# TIMB-E010-2.net
KiCad netlist of a schematic drawn in EAGLE
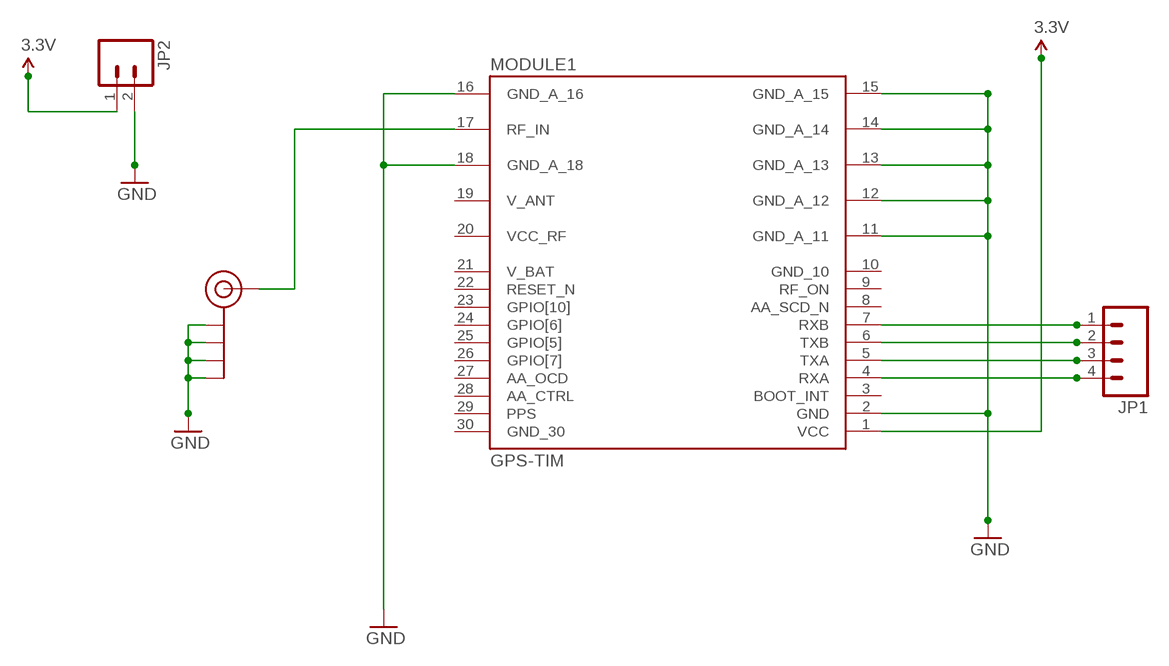
[diagram p0: schematic, sheet 1]

(export (version "E")
  (design (tool "Eeschema 10.0.6"))
  (components
    (comp (ref "J$1")
      (value "SMA_EDGE")
      (footprint "eagle-import:SMA-EDGE")
      (libsource (lib "eagle-import") (part "SMA_EDGE"))
    )
    (comp (ref "JP1")
      (value "M04LOCK")
      (footprint "eagle-import:1X04_LOCK")
      (libsource (lib "eagle-import") (part "M04LOCK"))
    )
    (comp (ref "JP2")
      (value "M02LOCK")
      (footprint "eagle-import:1X02_LOCK")
      (libsource (lib "eagle-import") (part "M02LOCK"))
    )
    (comp (ref "MODULE1")
      (value "GPS-TIM")
      (footprint "eagle-import:GPS_TIM")
      (libsource (lib "eagle-import") (part "GPS-TIM"))
    )
  )
  (nets
    (net (code "1") (name "3.3V") (class "Default")
      (node (ref "JP2") (pin "1") (pinfunction "1_1") (pintype "passive"))
      (node (ref "MODULE1") (pin "1") (pinfunction "VCC_1") (pintype "power_in"))
    )
    (net (code "2") (name "GND") (class "Default")
      (node (ref "J$1") (pin "GND@0") (pinfunction "GND_GND@0") (pintype "bidirectional"))
      (node (ref "J$1") (pin "GND@1") (pinfunction "GND_GND@1") (pintype "bidirectional"))
      (node (ref "J$1") (pin "GND@2") (pinfunction "GND_GND@2") (pintype "bidirectional"))
      (node (ref "J$1") (pin "GND@3") (pinfunction "GND_GND@3") (pintype "bidirectional"))
      (node (ref "JP2") (pin "2") (pinfunction "2_2") (pintype "passive"))
      (node (ref "MODULE1") (pin "11") (pinfunction "GND_A_11_11") (pintype "input"))
      (node (ref "MODULE1") (pin "12") (pinfunction "GND_A_12_12") (pintype "input"))
      (node (ref "MODULE1") (pin "13") (pinfunction "GND_A_13_13") (pintype "input"))
      (node (ref "MODULE1") (pin "14") (pinfunction "GND_A_14_14") (pintype "input"))
      (node (ref "MODULE1") (pin "15") (pinfunction "GND_A_15_15") (pintype "input"))
      (node (ref "MODULE1") (pin "16") (pinfunction "GND_A_16_16") (pintype "input"))
      (node (ref "MODULE1") (pin "18") (pinfunction "GND_A_18_18") (pintype "input"))
      (node (ref "MODULE1") (pin "2") (pinfunction "GND_2") (pintype "power_in"))
    )
    (net (code "3") (name "Net-(J$1-SIGNAL)") (class "Default")
      (node (ref "J$1") (pin "SIG") (pinfunction "SIGNAL_SIG") (pintype "bidirectional"))
      (node (ref "MODULE1") (pin "17") (pinfunction "RF_IN_17") (pintype "input"))
    )
    (net (code "4") (name "Net-(MODULE1-RXA)") (class "Default")
      (node (ref "JP1") (pin "4") (pinfunction "4_4") (pintype "passive"))
      (node (ref "MODULE1") (pin "4") (pinfunction "RXA_4") (pintype "input"))
    )
    (net (code "5") (name "Net-(MODULE1-RXB)") (class "Default")
      (node (ref "JP1") (pin "1") (pinfunction "1_1") (pintype "passive"))
      (node (ref "MODULE1") (pin "7") (pinfunction "RXB_7") (pintype "input"))
    )
    (net (code "6") (name "Net-(MODULE1-TXA)") (class "Default")
      (node (ref "JP1") (pin "3") (pinfunction "3_3") (pintype "passive"))
      (node (ref "MODULE1") (pin "5") (pinfunction "TXA_5") (pintype "output"))
    )
    (net (code "7") (name "Net-(MODULE1-TXB)") (class "Default")
      (node (ref "JP1") (pin "2") (pinfunction "2_2") (pintype "passive"))
      (node (ref "MODULE1") (pin "6") (pinfunction "TXB_6") (pintype "output"))
    )
    (net (code "8") (name "unconnected-(MODULE1-AA_CTRL-Pad28)") (class "Default")
      (node (ref "MODULE1") (pin "28") (pinfunction "AA_CTRL_28") (pintype "output"))
    )
    (net (code "9") (name "unconnected-(MODULE1-AA_OCD-Pad27)") (class "Default")
      (node (ref "MODULE1") (pin "27") (pinfunction "AA_OCD_27") (pintype "input"))
    )
    (net (code "10") (name "unconnected-(MODULE1-AA_SCD_N-Pad8)") (class "Default")
      (node (ref "MODULE1") (pin "8") (pinfunction "AA_SCD_N_8") (pintype "input"))
    )
    (net (code "11") (name "unconnected-(MODULE1-BOOT_INT-Pad3)") (class "Default")
      (node (ref "MODULE1") (pin "3") (pinfunction "BOOT_INT_3") (pintype "input"))
    )
    (net (code "12") (name "unconnected-(MODULE1-GND_10-Pad10)") (class "Default")
      (node (ref "MODULE1") (pin "10") (pinfunction "GND_10_10") (pintype "input"))
    )
    (net (code "13") (name "unconnected-(MODULE1-GND_30-Pad30)") (class "Default")
      (node (ref "MODULE1") (pin "30") (pinfunction "GND_30_30") (pintype "input"))
    )
    (net (code "14") (name "unconnected-(MODULE1-GPIO[5]-Pad25)") (class "Default")
      (node (ref "MODULE1") (pin "25") (pinfunction "GPIO[5]_25") (pintype "bidirectional"))
    )
    (net (code "15") (name "unconnected-(MODULE1-GPIO[6]-Pad24)") (class "Default")
      (node (ref "MODULE1") (pin "24") (pinfunction "GPIO[6]_24") (pintype "bidirectional"))
    )
    (net (code "16") (name "unconnected-(MODULE1-GPIO[7]-Pad26)") (class "Default")
      (node (ref "MODULE1") (pin "26") (pinfunction "GPIO[7]_26") (pintype "bidirectional"))
    )
    (net (code "17") (name "unconnected-(MODULE1-GPIO[10]-Pad23)") (class "Default")
      (node (ref "MODULE1") (pin "23") (pinfunction "GPIO[10]_23") (pintype "input"))
    )
    (net (code "18") (name "unconnected-(MODULE1-PPS-Pad29)") (class "Default")
      (node (ref "MODULE1") (pin "29") (pinfunction "PPS_29") (pintype "output"))
    )
    (net (code "19") (name "unconnected-(MODULE1-RESET_N-Pad22)") (class "Default")
      (node (ref "MODULE1") (pin "22") (pinfunction "RESET_N_22") (pintype "input"))
    )
    (net (code "20") (name "unconnected-(MODULE1-RF_ON-Pad9)") (class "Default")
      (node (ref "MODULE1") (pin "9") (pinfunction "RF_ON_9") (pintype "output"))
    )
    (net (code "21") (name "unconnected-(MODULE1-VCC_RF-Pad20)") (class "Default")
      (node (ref "MODULE1") (pin "20") (pinfunction "VCC_RF_20") (pintype "output"))
    )
    (net (code "22") (name "unconnected-(MODULE1-V_ANT-Pad19)") (class "Default")
      (node (ref "MODULE1") (pin "19") (pinfunction "V_ANT_19") (pintype "input"))
    )
    (net (code "23") (name "unconnected-(MODULE1-V_BAT-Pad21)") (class "Default")
      (node (ref "MODULE1") (pin "21") (pinfunction "V_BAT_21") (pintype "input"))
    )
  )
)
